# Motor_Driver.net
KiCad netlist of a schematic drawn in EAGLE
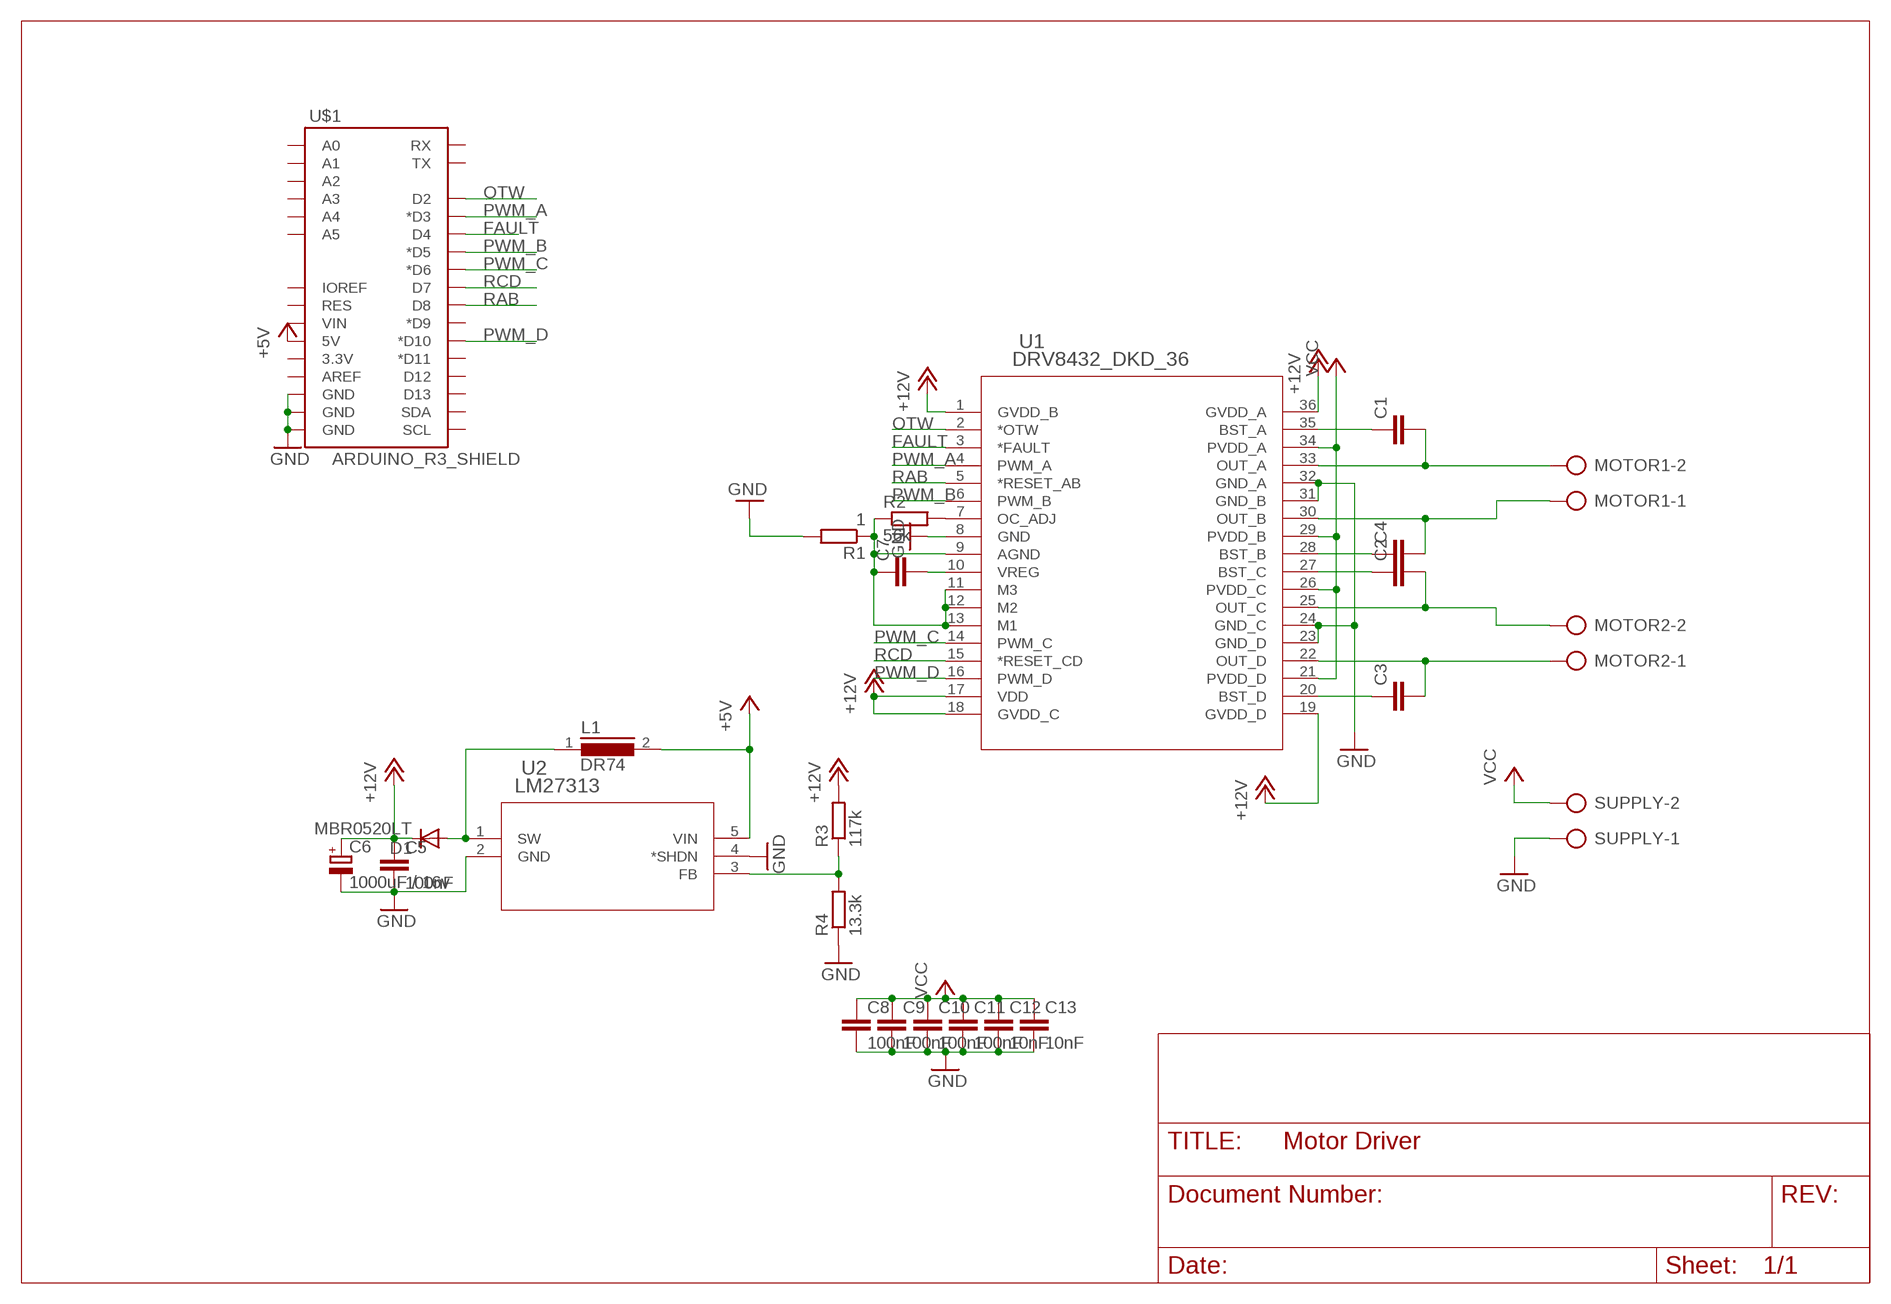
[diagram p0: schematic, sheet 1]

(export (version "E")
  (design (tool "Eeschema 10.0.6"))
  (components
    (comp (ref "C1")
      (value "C-EUC0402K")
      (footprint "eagle-import:C0402K")
      (libsource (lib "eagle-import") (part "C-EUC0402K"))
    )
    (comp (ref "C2")
      (value "C-EUC0402K")
      (footprint "eagle-import:C0402K")
      (libsource (lib "eagle-import") (part "C-EUC0402K"))
    )
    (comp (ref "C3")
      (value "C-EUC0402K")
      (footprint "eagle-import:C0402K")
      (libsource (lib "eagle-import") (part "C-EUC0402K"))
    )
    (comp (ref "C4")
      (value "C-EUC0402K")
      (footprint "eagle-import:C0402K")
      (libsource (lib "eagle-import") (part "C-EUC0402K"))
    )
    (comp (ref "C5")
      (value "100nF")
      (footprint "eagle-import:C0805K")
      (libsource (lib "eagle-import") (part "C-EUC0805K"))
    )
    (comp (ref "C6")
      (value "1000uF / 16v")
      (footprint "eagle-import:B45181B")
      (libsource (lib "eagle-import") (part "CPOL-EUB45181B"))
    )
    (comp (ref "C7")
      (value "C-EUC0805K")
      (footprint "eagle-import:C0805K")
      (libsource (lib "eagle-import") (part "C-EUC0805K"))
    )
    (comp (ref "C8")
      (value "100nF")
      (footprint "eagle-import:C0805K")
      (libsource (lib "eagle-import") (part "C-EUC0805K"))
    )
    (comp (ref "C9")
      (value "100nF")
      (footprint "eagle-import:C0805K")
      (libsource (lib "eagle-import") (part "C-EUC0805K"))
    )
    (comp (ref "C10")
      (value "100nF")
      (footprint "eagle-import:C0805K")
      (libsource (lib "eagle-import") (part "C-EUC0805K"))
    )
    (comp (ref "C11")
      (value "100nF")
      (footprint "eagle-import:C0805K")
      (libsource (lib "eagle-import") (part "C-EUC0805K"))
    )
    (comp (ref "C12")
      (value "10nF")
      (footprint "eagle-import:C0805K")
      (libsource (lib "eagle-import") (part "C-EUC0805K"))
    )
    (comp (ref "C13")
      (value "10nF")
      (footprint "eagle-import:C0805K")
      (libsource (lib "eagle-import") (part "C-EUC0805K"))
    )
    (comp (ref "D1")
      (value "MBR0520LT")
      (footprint "eagle-import:SOD123")
      (libsource (lib "eagle-import") (part "MBR0520LT"))
    )
    (comp (ref "L1")
      (value "DR74")
      (footprint "eagle-import:DR74")
      (libsource (lib "eagle-import") (part "DR74"))
    )
    (comp (ref "MOTOR1")
      (value "AK300/2")
      (footprint "eagle-import:AK300_2")
      (libsource (lib "eagle-import") (part "AK300/2"))
    )
    (comp (ref "MOTOR2")
      (value "AK300/2")
      (footprint "eagle-import:AK300_2")
      (libsource (lib "eagle-import") (part "AK300/2"))
    )
    (comp (ref "R1")
      (value "1")
      (footprint "eagle-import:M0805")
      (libsource (lib "eagle-import") (part "R-EU_M0805"))
    )
    (comp (ref "R2")
      (value "56k")
      (footprint "eagle-import:M0805")
      (libsource (lib "eagle-import") (part "R-EU_M0805"))
    )
    (comp (ref "R3")
      (value "117k")
      (footprint "eagle-import:R0805")
      (libsource (lib "eagle-import") (part "R-EU_R0805"))
    )
    (comp (ref "R4")
      (value "13.3k")
      (footprint "eagle-import:R0805")
      (libsource (lib "eagle-import") (part "R-EU_R0805"))
    )
    (comp (ref "SUPPLY")
      (value "AK300/2")
      (footprint "eagle-import:AK300_2")
      (libsource (lib "eagle-import") (part "AK300/2"))
    )
    (comp (ref "U$1")
      (value "ARDUINO_R3_SHIELD")
      (footprint "eagle-import:UNO_R3_SHIELD")
      (libsource (lib "eagle-import") (part "ARDUINO_R3_SHIELD"))
    )
    (comp (ref "U1")
      (value "DRV8432_DKD_36")
      (footprint "eagle-import:DKD36")
      (fields
        (field (name "GENERIC_PART_NUMBER") "DRV8432")
        (field (name "MANUFACTURER") "Texas Instruments")
        (field (name "MANUFACTURER_PART_NUMBER") "drv8432_dkd_36")
      )
      (libsource (lib "eagle-import") (part "DRV8432_DKD_36"))
    )
    (comp (ref "U2")
      (value "LM27313")
      (footprint "eagle-import:MF05A")
      (fields
        (field (name "MANUFACTURER") "Texas Instruments")
        (field (name "MANUFACTURER_PART_NUMBER") "lm27313_dbv_5")
      )
      (libsource (lib "eagle-import") (part "LM27313"))
    )
  )
  (nets
    (net (code "1") (name "+5V") (class "Default")
      (node (ref "L1") (pin "2") (pinfunction "2_2") (pintype "passive"))
      (node (ref "U$1") (pin "5V") (pinfunction "5V_5V") (pintype "bidirectional"))
      (node (ref "U2") (pin "5") (pinfunction "VIN_5") (pintype "input"))
    )
    (net (code "2") (name "+12V") (class "Default")
      (node (ref "C5") (pin "1") (pinfunction "1_1") (pintype "passive"))
      (node (ref "C6") (pin "+") (pinfunction "+_+") (pintype "passive"))
      (node (ref "D1") (pin "C") (pinfunction "C_C") (pintype "passive"))
      (node (ref "R3") (pin "2") (pinfunction "2_2") (pintype "passive"))
      (node (ref "U1") (pin "1") (pinfunction "GVDD_B_1") (pintype "power_in"))
      (node (ref "U1") (pin "17") (pinfunction "VDD_17") (pintype "power_in"))
      (node (ref "U1") (pin "18") (pinfunction "GVDD_C_18") (pintype "power_in"))
      (node (ref "U1") (pin "19") (pinfunction "GVDD_D_19") (pintype "power_in"))
      (node (ref "U1") (pin "36") (pinfunction "GVDD_A_36") (pintype "power_in"))
    )
    (net (code "3") (name "/FAULT") (class "Default")
      (node (ref "U$1") (pin "D4") (pinfunction "D4_D4") (pintype "bidirectional"))
      (node (ref "U1") (pin "3") (pinfunction "*FAULT_3") (pintype "output"))
    )
    (net (code "4") (name "/OTW") (class "Default")
      (node (ref "U$1") (pin "D2") (pinfunction "D2_D2") (pintype "bidirectional"))
      (node (ref "U1") (pin "2") (pinfunction "*OTW_2") (pintype "output"))
    )
    (net (code "5") (name "/PWM_A") (class "Default")
      (node (ref "U$1") (pin "D3") (pinfunction "*D3_D3") (pintype "bidirectional"))
      (node (ref "U1") (pin "4") (pinfunction "PWM_A_4") (pintype "input"))
    )
    (net (code "6") (name "/PWM_B") (class "Default")
      (node (ref "U$1") (pin "D5") (pinfunction "*D5_D5") (pintype "bidirectional"))
      (node (ref "U1") (pin "6") (pinfunction "PWM_B_6") (pintype "input"))
    )
    (net (code "7") (name "/PWM_C") (class "Default")
      (node (ref "U$1") (pin "D6") (pinfunction "*D6_D6") (pintype "bidirectional"))
      (node (ref "U1") (pin "14") (pinfunction "PWM_C_14") (pintype "input"))
    )
    (net (code "8") (name "/PWM_D") (class "Default")
      (node (ref "U$1") (pin "D10") (pinfunction "*D10_D10") (pintype "bidirectional"))
      (node (ref "U1") (pin "16") (pinfunction "PWM_D_16") (pintype "input"))
    )
    (net (code "9") (name "/RAB") (class "Default")
      (node (ref "U$1") (pin "D8") (pinfunction "D8_D8") (pintype "bidirectional"))
      (node (ref "U1") (pin "5") (pinfunction "*RESET_AB_5") (pintype "input"))
    )
    (net (code "10") (name "/RCD") (class "Default")
      (node (ref "U$1") (pin "D7") (pinfunction "D7_D7") (pintype "bidirectional"))
      (node (ref "U1") (pin "15") (pinfunction "*RESET_CD_15") (pintype "input"))
    )
    (net (code "11") (name "GND") (class "Default")
      (node (ref "C10") (pin "2") (pinfunction "2_2") (pintype "passive"))
      (node (ref "C11") (pin "2") (pinfunction "2_2") (pintype "passive"))
      (node (ref "C12") (pin "2") (pinfunction "2_2") (pintype "passive"))
      (node (ref "C13") (pin "2") (pinfunction "2_2") (pintype "passive"))
      (node (ref "C5") (pin "2") (pinfunction "2_2") (pintype "passive"))
      (node (ref "C6") (pin "-") (pinfunction "-_-") (pintype "passive"))
      (node (ref "C8") (pin "2") (pinfunction "2_2") (pintype "passive"))
      (node (ref "C9") (pin "2") (pinfunction "2_2") (pintype "passive"))
      (node (ref "R1") (pin "2") (pinfunction "2_2") (pintype "passive"))
      (node (ref "R4") (pin "1") (pinfunction "1_1") (pintype "passive"))
      (node (ref "SUPPLY") (pin "1") (pinfunction "KL_1") (pintype "passive"))
      (node (ref "U$1") (pin "GND@0") (pinfunction "GND_GND@0") (pintype "bidirectional"))
      (node (ref "U$1") (pin "GND@1") (pinfunction "GND_GND@1") (pintype "bidirectional"))
      (node (ref "U$1") (pin "GND@2") (pinfunction "GND_GND@2") (pintype "bidirectional"))
      (node (ref "U1") (pin "23") (pinfunction "GND_D_23") (pintype "power_in"))
      (node (ref "U1") (pin "24") (pinfunction "GND_C_24") (pintype "power_in"))
      (node (ref "U1") (pin "31") (pinfunction "GND_B_31") (pintype "power_in"))
      (node (ref "U1") (pin "32") (pinfunction "GND_A_32") (pintype "power_in"))
      (node (ref "U1") (pin "8") (pinfunction "GND_8") (pintype "power_in"))
      (node (ref "U2") (pin "2") (pinfunction "GND_2") (pintype "power_in"))
      (node (ref "U2") (pin "4") (pinfunction "*SHDN_4") (pintype "input"))
    )
    (net (code "12") (name "Net-(MOTOR1A-KL)") (class "Default")
      (node (ref "C4") (pin "2") (pinfunction "2_2") (pintype "passive"))
      (node (ref "MOTOR1") (pin "1") (pinfunction "KL_1") (pintype "passive"))
      (node (ref "U1") (pin "30") (pinfunction "OUT_B_30") (pintype "output"))
    )
    (net (code "13") (name "Net-(MOTOR1B-KL)") (class "Default")
      (node (ref "C1") (pin "2") (pinfunction "2_2") (pintype "passive"))
      (node (ref "MOTOR1") (pin "2") (pinfunction "KL_2") (pintype "passive"))
      (node (ref "U1") (pin "33") (pinfunction "OUT_A_33") (pintype "output"))
    )
    (net (code "14") (name "Net-(MOTOR2A-KL)") (class "Default")
      (node (ref "C3") (pin "2") (pinfunction "2_2") (pintype "passive"))
      (node (ref "MOTOR2") (pin "1") (pinfunction "KL_1") (pintype "passive"))
      (node (ref "U1") (pin "22") (pinfunction "OUT_D_22") (pintype "output"))
    )
    (net (code "15") (name "Net-(MOTOR2B-KL)") (class "Default")
      (node (ref "C2") (pin "2") (pinfunction "2_2") (pintype "passive"))
      (node (ref "MOTOR2") (pin "2") (pinfunction "KL_2") (pintype "passive"))
      (node (ref "U1") (pin "25") (pinfunction "OUT_C_25") (pintype "output"))
    )
    (net (code "16") (name "Net-(U1-AGND)") (class "Default")
      (node (ref "C7") (pin "1") (pinfunction "1_1") (pintype "passive"))
      (node (ref "R1") (pin "1") (pinfunction "1_1") (pintype "passive"))
      (node (ref "R2") (pin "1") (pinfunction "1_1") (pintype "passive"))
      (node (ref "U1") (pin "11") (pinfunction "M3_11") (pintype "input"))
      (node (ref "U1") (pin "12") (pinfunction "M2_12") (pintype "input"))
      (node (ref "U1") (pin "13") (pinfunction "M1_13") (pintype "input"))
      (node (ref "U1") (pin "9") (pinfunction "AGND_9") (pintype "power_in"))
    )
    (net (code "17") (name "Net-(U1-BST_A)") (class "Default")
      (node (ref "C1") (pin "1") (pinfunction "1_1") (pintype "passive"))
      (node (ref "U1") (pin "35") (pinfunction "BST_A_35") (pintype "power_in"))
    )
    (net (code "18") (name "Net-(U1-BST_B)") (class "Default")
      (node (ref "C4") (pin "1") (pinfunction "1_1") (pintype "passive"))
      (node (ref "U1") (pin "28") (pinfunction "BST_B_28") (pintype "power_in"))
    )
    (net (code "19") (name "Net-(U1-BST_C)") (class "Default")
      (node (ref "C2") (pin "1") (pinfunction "1_1") (pintype "passive"))
      (node (ref "U1") (pin "27") (pinfunction "BST_C_27") (pintype "power_in"))
    )
    (net (code "20") (name "Net-(U1-BST_D)") (class "Default")
      (node (ref "C3") (pin "1") (pinfunction "1_1") (pintype "passive"))
      (node (ref "U1") (pin "20") (pinfunction "BST_D_20") (pintype "power_in"))
    )
    (net (code "21") (name "Net-(U1-OC_ADJ)") (class "Default")
      (node (ref "R2") (pin "2") (pinfunction "2_2") (pintype "passive"))
      (node (ref "U1") (pin "7") (pinfunction "OC_ADJ_7") (pintype "output"))
    )
    (net (code "22") (name "Net-(U1-VREG)") (class "Default")
      (node (ref "C7") (pin "2") (pinfunction "2_2") (pintype "passive"))
      (node (ref "U1") (pin "10") (pinfunction "VREG_10") (pintype "power_in"))
    )
    (net (code "23") (name "Net-(U2-FB)") (class "Default")
      (node (ref "R3") (pin "1") (pinfunction "1_1") (pintype "passive"))
      (node (ref "R4") (pin "2") (pinfunction "2_2") (pintype "passive"))
      (node (ref "U2") (pin "3") (pinfunction "FB_3") (pintype "passive"))
    )
    (net (code "24") (name "Net-(U2-SW)") (class "Default")
      (node (ref "D1") (pin "A") (pinfunction "A_A") (pintype "passive"))
      (node (ref "L1") (pin "1") (pinfunction "1_1") (pintype "passive"))
      (node (ref "U2") (pin "1") (pinfunction "SW_1") (pintype "passive"))
    )
    (net (code "25") (name "VCC") (class "Default")
      (node (ref "C10") (pin "1") (pinfunction "1_1") (pintype "passive"))
      (node (ref "C11") (pin "1") (pinfunction "1_1") (pintype "passive"))
      (node (ref "C12") (pin "1") (pinfunction "1_1") (pintype "passive"))
      (node (ref "C13") (pin "1") (pinfunction "1_1") (pintype "passive"))
      (node (ref "C8") (pin "1") (pinfunction "1_1") (pintype "passive"))
      (node (ref "C9") (pin "1") (pinfunction "1_1") (pintype "passive"))
      (node (ref "SUPPLY") (pin "2") (pinfunction "KL_2") (pintype "passive"))
      (node (ref "U1") (pin "21") (pinfunction "PVDD_D_21") (pintype "power_in"))
      (node (ref "U1") (pin "26") (pinfunction "PVDD_C_26") (pintype "power_in"))
      (node (ref "U1") (pin "29") (pinfunction "PVDD_B_29") (pintype "power_in"))
      (node (ref "U1") (pin "34") (pinfunction "PVDD_A_34") (pintype "power_in"))
    )
    (net (code "26") (name "unconnected-(U$1-*D9-PadD9)") (class "Default")
      (node (ref "U$1") (pin "D9") (pinfunction "*D9_D9") (pintype "bidirectional"))
    )
    (net (code "27") (name "unconnected-(U$1-*D11-PadD11)") (class "Default")
      (node (ref "U$1") (pin "D11") (pinfunction "*D11_D11") (pintype "bidirectional"))
    )
    (net (code "28") (name "unconnected-(U$1-Pad3.3V)") (class "Default")
      (node (ref "U$1") (pin "3.3V") (pinfunction "3.3V_3.3V") (pintype "bidirectional"))
    )
    (net (code "29") (name "unconnected-(U$1-PadA0)") (class "Default")
      (node (ref "U$1") (pin "A0") (pinfunction "A0_A0") (pintype "bidirectional"))
    )
    (net (code "30") (name "unconnected-(U$1-PadA1)") (class "Default")
      (node (ref "U$1") (pin "A1") (pinfunction "A1_A1") (pintype "bidirectional"))
    )
    (net (code "31") (name "unconnected-(U$1-PadA2)") (class "Default")
      (node (ref "U$1") (pin "A2") (pinfunction "A2_A2") (pintype "bidirectional"))
    )
    (net (code "32") (name "unconnected-(U$1-PadA3)") (class "Default")
      (node (ref "U$1") (pin "A3") (pinfunction "A3_A3") (pintype "bidirectional"))
    )
    (net (code "33") (name "unconnected-(U$1-PadA4)") (class "Default")
      (node (ref "U$1") (pin "A4") (pinfunction "A4_A4") (pintype "bidirectional"))
    )
    (net (code "34") (name "unconnected-(U$1-PadA5)") (class "Default")
      (node (ref "U$1") (pin "A5") (pinfunction "A5_A5") (pintype "bidirectional"))
    )
    (net (code "35") (name "unconnected-(U$1-PadAREF)") (class "Default")
      (node (ref "U$1") (pin "AREF") (pinfunction "AREF_AREF") (pintype "bidirectional"))
    )
    (net (code "36") (name "unconnected-(U$1-PadD12)") (class "Default")
      (node (ref "U$1") (pin "D12") (pinfunction "D12_D12") (pintype "bidirectional"))
    )
    (net (code "37") (name "unconnected-(U$1-PadD13)") (class "Default")
      (node (ref "U$1") (pin "D13") (pinfunction "D13_D13") (pintype "bidirectional"))
    )
    (net (code "38") (name "unconnected-(U$1-PadIOREF)") (class "Default")
      (node (ref "U$1") (pin "IOREF") (pinfunction "IOREF_IOREF") (pintype "bidirectional"))
    )
    (net (code "39") (name "unconnected-(U$1-PadRES)") (class "Default")
      (node (ref "U$1") (pin "RES") (pinfunction "RES_RES") (pintype "bidirectional"))
    )
    (net (code "40") (name "unconnected-(U$1-PadRX)") (class "Default")
      (node (ref "U$1") (pin "RX") (pinfunction "RX_RX") (pintype "bidirectional"))
    )
    (net (code "41") (name "unconnected-(U$1-PadSCL)") (class "Default")
      (node (ref "U$1") (pin "SCL") (pinfunction "SCL_SCL") (pintype "bidirectional"))
    )
    (net (code "42") (name "unconnected-(U$1-PadSDA)") (class "Default")
      (node (ref "U$1") (pin "SDA") (pinfunction "SDA_SDA") (pintype "bidirectional"))
    )
    (net (code "43") (name "unconnected-(U$1-PadTX)") (class "Default")
      (node (ref "U$1") (pin "TX") (pinfunction "TX_TX") (pintype "bidirectional"))
    )
    (net (code "44") (name "unconnected-(U$1-PadVIN)") (class "Default")
      (node (ref "U$1") (pin "VIN") (pinfunction "VIN_VIN") (pintype "bidirectional"))
    )
  )
)
